# Logica_ADC.net
KiCad netlist of a schematic drawn in Altium Designer
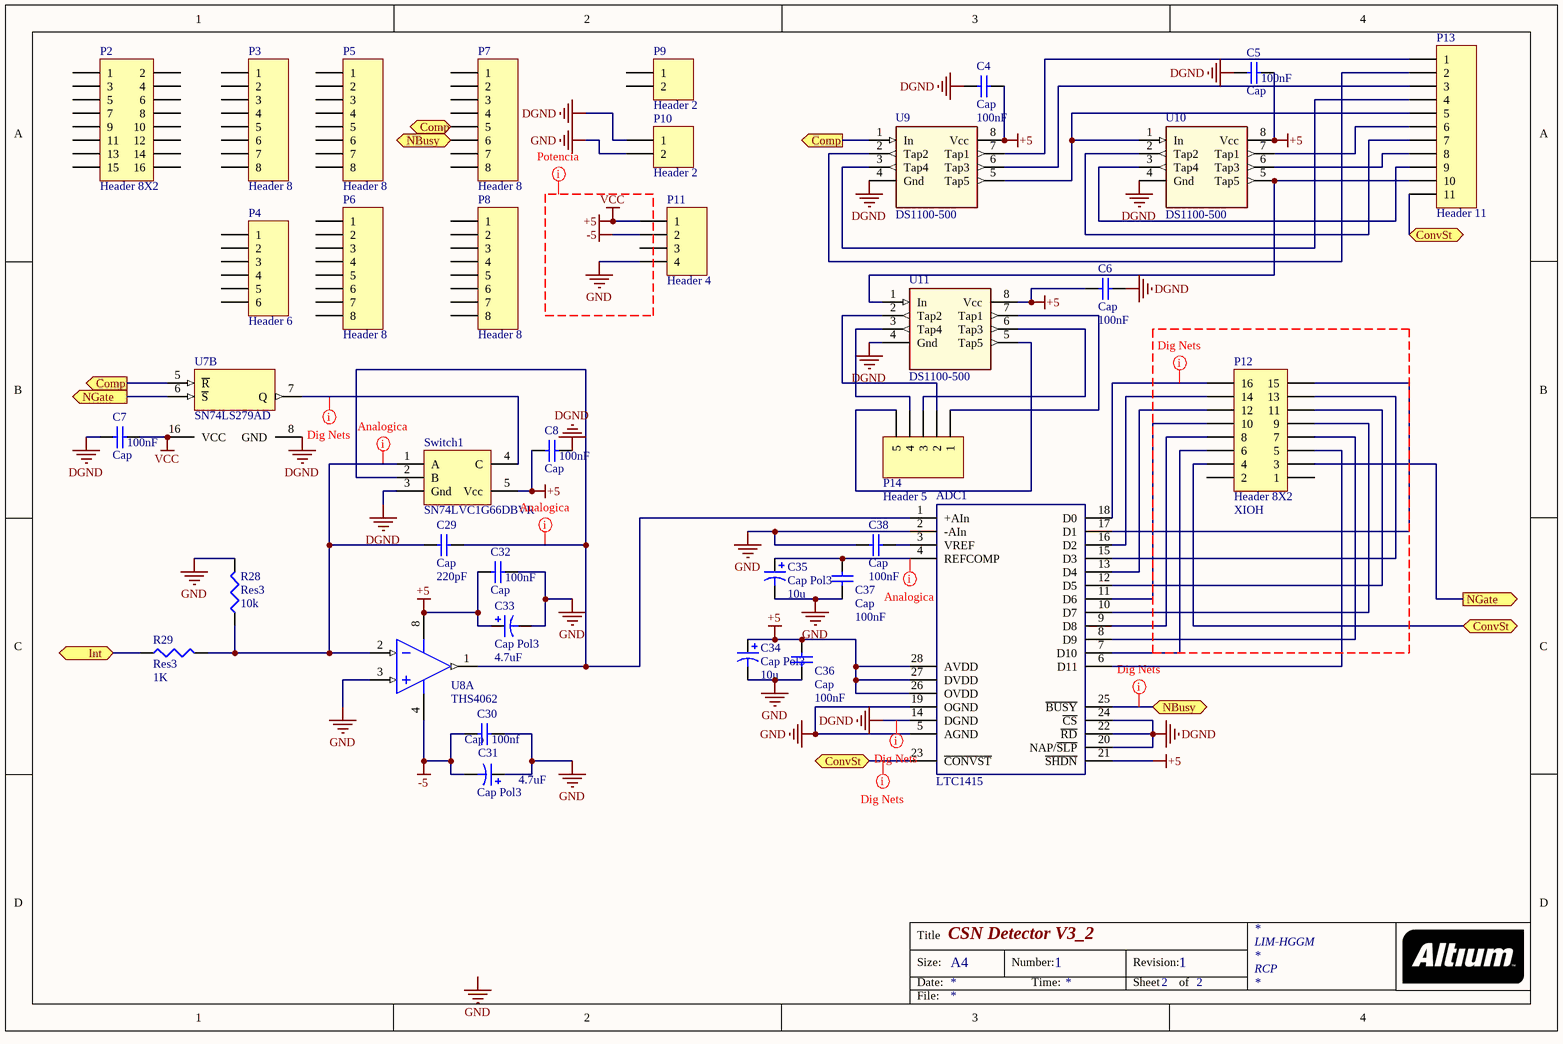
[diagram p0: Logica_ADC.SchDoc]

(export (version "E")
  (design (tool "Eeschema 10.0.6"))
  (components
    (comp (ref "ADC1")
      (value "LTC1415")
      (footprint "SO28_N")
      (libsource (lib "Integrated_Library1") (part "LTC1415"))
    )
    (comp (ref "C4")
      (value "Cap")
      (footprint "6-0805_N")
      (description "Capacitor")
      (fields (field (name "ALTIUM_VALUE") "100nF") (field (name "PUBLISHER") "Altium Limited"))
      (libsource (lib "Miscellaneous Devices") (part "Cap"))
    )
    (comp (ref "C5")
      (value "Cap")
      (footprint "6-0805_N")
      (description "Capacitor")
      (fields (field (name "ALTIUM_VALUE") "100nF") (field (name "PUBLISHER") "Altium Limited"))
      (libsource (lib "Miscellaneous Devices") (part "Cap"))
    )
    (comp (ref "C6")
      (value "Cap")
      (footprint "6-0805_N")
      (description "Capacitor")
      (fields (field (name "ALTIUM_VALUE") "100nF") (field (name "PUBLISHER") "Altium Limited"))
      (libsource (lib "Miscellaneous Devices") (part "Cap"))
    )
    (comp (ref "C7")
      (value "Cap")
      (footprint "6-0805_N")
      (description "Capacitor")
      (fields (field (name "ALTIUM_VALUE") "100nF") (field (name "PUBLISHER") "Altium Limited"))
      (libsource (lib "Miscellaneous Devices") (part "Cap"))
    )
    (comp (ref "C8")
      (value "Cap")
      (footprint "6-0805_N")
      (description "Capacitor")
      (fields (field (name "ALTIUM_VALUE") "100nF") (field (name "PUBLISHER") "Altium Limited"))
      (libsource (lib "Miscellaneous Devices") (part "Cap"))
    )
    (comp (ref "C29")
      (value "Cap")
      (footprint "6-0805_N")
      (description "Capacitor")
      (fields (field (name "ALTIUM_VALUE") "220pF") (field (name "PUBLISHER") "Altium Limited"))
      (libsource (lib "Miscellaneous Devices") (part "Cap"))
    )
    (comp (ref "C30")
      (value "Cap")
      (footprint "6-0805_N")
      (description "Capacitor")
      (fields (field (name "ALTIUM_VALUE") "100nf") (field (name "PUBLISHER") "Altium Limited"))
      (libsource (lib "Miscellaneous Devices") (part "Cap"))
    )
    (comp (ref "C31")
      (value "Cap Pol3")
      (footprint "6-0805_N")
      (description "Polarized Capacitor (Surface Mount)")
      (fields (field (name "ALTIUM_VALUE") "4.7uF") (field (name "PUBLISHER") "Altium Limited"))
      (libsource (lib "Miscellaneous Devices") (part "Cap Pol3"))
    )
    (comp (ref "C32")
      (value "Cap")
      (footprint "6-0805_N")
      (description "Capacitor")
      (fields (field (name "ALTIUM_VALUE") "100nF") (field (name "PUBLISHER") "Altium Limited"))
      (libsource (lib "Miscellaneous Devices") (part "Cap"))
    )
    (comp (ref "C33")
      (value "Cap Pol3")
      (footprint "6-0805_N")
      (description "Polarized Capacitor (Surface Mount)")
      (fields (field (name "ALTIUM_VALUE") "4.7uF") (field (name "PUBLISHER") "Altium Limited"))
      (libsource (lib "Miscellaneous Devices") (part "Cap Pol3"))
    )
    (comp (ref "C34")
      (value "Cap Pol3")
      (footprint "6-0805_N")
      (description "Polarized Capacitor (Surface Mount)")
      (fields (field (name "ALTIUM_VALUE") "10u") (field (name "PUBLISHER") "Altium Limited"))
      (libsource (lib "Miscellaneous Devices") (part "Cap Pol3"))
    )
    (comp (ref "C35")
      (value "Cap Pol3")
      (footprint "6-0805_N")
      (description "Polarized Capacitor (Surface Mount)")
      (fields (field (name "ALTIUM_VALUE") "10u") (field (name "PUBLISHER") "Altium Limited"))
      (libsource (lib "Miscellaneous Devices") (part "Cap Pol3"))
    )
    (comp (ref "C36")
      (value "Cap")
      (footprint "6-0805_N")
      (description "Capacitor")
      (fields (field (name "ALTIUM_VALUE") "100nF") (field (name "PUBLISHER") "Altium Limited"))
      (libsource (lib "Miscellaneous Devices") (part "Cap"))
    )
    (comp (ref "C37")
      (value "Cap")
      (footprint "6-0805_N")
      (description "Capacitor")
      (fields (field (name "ALTIUM_VALUE") "100nF") (field (name "PUBLISHER") "Altium Limited"))
      (libsource (lib "Miscellaneous Devices") (part "Cap"))
    )
    (comp (ref "C38")
      (value "Cap")
      (footprint "6-0805_N")
      (description "Capacitor")
      (fields (field (name "ALTIUM_VALUE") "100nF") (field (name "PUBLISHER") "Altium Limited"))
      (libsource (lib "Miscellaneous Devices") (part "Cap"))
    )
    (comp (ref "P2")
      (value "Header 8X2")
      (footprint "HDR2X8")
      (description "Header, 8-Pin, Dual row")
      (fields (field (name "PUBLISHER") "Altium Limited"))
      (libsource (lib "Miscellaneous Connectors") (part "Header 8X2"))
    )
    (comp (ref "P3")
      (value "Header 8")
      (footprint "HDR1X8")
      (description "Header, 8-Pin")
      (fields (field (name "PUBLISHER") "Altium Limited"))
      (libsource (lib "Miscellaneous Connectors") (part "Header 8"))
    )
    (comp (ref "P4")
      (value "Header 6")
      (footprint "HDR1X6")
      (description "Header, 6-Pin")
      (fields (field (name "PUBLISHER") "Altium Limited"))
      (libsource (lib "Miscellaneous Connectors") (part "Header 6"))
    )
    (comp (ref "P5")
      (value "Header 8")
      (footprint "HDR1X8")
      (description "Header, 8-Pin")
      (fields (field (name "PUBLISHER") "Altium Limited"))
      (libsource (lib "Miscellaneous Connectors") (part "Header 8"))
    )
    (comp (ref "P6")
      (value "Header 8")
      (footprint "HDR1X8")
      (description "Header, 8-Pin")
      (fields (field (name "PUBLISHER") "Altium Limited"))
      (libsource (lib "Miscellaneous Connectors") (part "Header 8"))
    )
    (comp (ref "P7")
      (value "Header 8")
      (footprint "HDR1X8")
      (description "Header, 8-Pin")
      (fields (field (name "PUBLISHER") "Altium Limited"))
      (libsource (lib "Miscellaneous Connectors") (part "Header 8"))
    )
    (comp (ref "P8")
      (value "Header 8")
      (footprint "HDR1X8")
      (description "Header, 8-Pin")
      (fields (field (name "PUBLISHER") "Altium Limited"))
      (libsource (lib "Miscellaneous Connectors") (part "Header 8"))
    )
    (comp (ref "P9")
      (value "Header 2")
      (footprint "HDR1X2")
      (description "Header, 2-Pin")
      (fields (field (name "PUBLISHER") "Altium Limited"))
      (libsource (lib "Miscellaneous Connectors") (part "Header 2"))
    )
    (comp (ref "P10")
      (value "Header 2")
      (footprint "HDR1X2")
      (description "Header, 2-Pin")
      (fields (field (name "PUBLISHER") "Altium Limited"))
      (libsource (lib "Miscellaneous Connectors") (part "Header 2"))
    )
    (comp (ref "P11")
      (value "Header 4")
      (footprint "HDR1X4")
      (description "Header, 4-Pin")
      (fields (field (name "PUBLISHER") "Altium Limited"))
      (libsource (lib "Miscellaneous Connectors") (part "Header 4"))
    )
    (comp (ref "P12")
      (value "Header 8X2")
      (footprint "HDR2X8")
      (description "Header, 8-Pin, Dual row")
      (fields (field (name "CON_ARDUINO") "XIOH") (field (name "PUBLISHER") "Altium Limited"))
      (libsource (lib "") (part "Header 8X2_1"))
    )
    (comp (ref "P13")
      (value "Header 11")
      (footprint "HDR1X11")
      (description "Header, 11-Pin")
      (fields (field (name "PUBLISHER") "Altium Limited"))
      (libsource (lib "Miscellaneous Connectors") (part "Header 11"))
    )
    (comp (ref "P14")
      (value "Header 5")
      (footprint "HDR1X5")
      (description "Header, 5-Pin")
      (fields (field (name "PUBLISHER") "Altium Limited"))
      (libsource (lib "Miscellaneous Connectors") (part "Header 5"))
    )
    (comp (ref "R28")
      (value "Res3")
      (footprint "6-0805_N")
      (description "Resistor")
      (fields (field (name "ALTIUM_VALUE") "10k") (field (name "PUBLISHER") "Altium Limited"))
      (libsource (lib "Miscellaneous Devices") (part "Res3"))
    )
    (comp (ref "R29")
      (value "Res3")
      (footprint "6-0805_N")
      (description "Resistor")
      (fields (field (name "ALTIUM_VALUE") "1K") (field (name "PUBLISHER") "Altium Limited"))
      (libsource (lib "Miscellaneous Devices") (part "Res3"))
    )
    (comp (ref "Switch1")
      (value "SN74LVC1G66DBVR")
      (footprint "SOT23-5_N")
      (libsource (lib "Integrated_Library1") (part "SN74LVC1G66DBVR"))
    )
    (comp (ref "U7")
      (value "SN74LS279AD")
      (footprint "D016_N")
      (description "Quadruple S-R Latches")
      (fields (field (name "PUBLISHER") "Altium Limited"))
      (libsource (lib "TI Logic Latch") (part "SN74LS279AD"))
    )
    (comp (ref "U8")
      (value "THS4062")
      (footprint "S8_N")
      (description "Low Cost Dual Video Amplifier")
      (fields (field (name "PUBLISHER") "Altium Limited"))
      (libsource (lib "LT Video Amplifier") (part "LT1253CS8"))
    )
    (comp (ref "U9")
      (value "DS1100-500")
      (footprint "SO-8_L")
      (libsource (lib "Int_Lib1") (part "DS1100-500"))
    )
    (comp (ref "U10")
      (value "DS1100-500")
      (footprint "SO-8_L")
      (libsource (lib "Int_Lib1") (part "DS1100-500"))
    )
    (comp (ref "U11")
      (value "DS1100-500")
      (footprint "SO-8_L")
      (libsource (lib "Int_Lib1") (part "DS1100-500"))
    )
  )
  (nets
    (net (code "1") (name "+5") (class "Default")
      (node (ref "ADC1") (pin "21") (pinfunction "~{SHDN}_21") (pintype "passive"))
      (node (ref "ADC1") (pin "26") (pinfunction "OVDD_26") (pintype "passive"))
      (node (ref "ADC1") (pin "27") (pinfunction "DVDD_27") (pintype "passive"))
      (node (ref "ADC1") (pin "28") (pinfunction "AVDD_28") (pintype "passive"))
      (node (ref "C32") (pin "2") (pinfunction "2_2") (pintype "passive"))
      (node (ref "C33") (pin "1") (pinfunction "1_1") (pintype "passive"))
      (node (ref "C34") (pin "1") (pinfunction "1_1") (pintype "passive"))
      (node (ref "C36") (pin "2") (pinfunction "2_2") (pintype "passive"))
      (node (ref "C4") (pin "2") (pinfunction "2_2") (pintype "passive"))
      (node (ref "C5") (pin "1") (pinfunction "1_1") (pintype "passive"))
      (node (ref "C6") (pin "1") (pinfunction "1_1") (pintype "passive"))
      (node (ref "C7") (pin "1") (pinfunction "1_1") (pintype "passive"))
      (node (ref "C8") (pin "2") (pinfunction "2_2") (pintype "passive"))
      (node (ref "P11") (pin "1") (pinfunction "1_1") (pintype "passive"))
      (node (ref "Switch1") (pin "5") (pinfunction "Vcc_5") (pintype "passive"))
      (node (ref "U10") (pin "8") (pinfunction "Vcc_8") (pintype "power_in"))
      (node (ref "U11") (pin "8") (pinfunction "Vcc_8") (pintype "power_in"))
      (node (ref "U7") (pin "16") (pinfunction "VCC_16") (pintype "power_in"))
      (node (ref "U8") (pin "8") (pinfunction "V+_8") (pintype "power_in"))
      (node (ref "U9") (pin "8") (pinfunction "Vcc_8") (pintype "power_in"))
    )
    (net (code "2") (name "-5") (class "Default")
      (node (ref "C30") (pin "1") (pinfunction "1_1") (pintype "passive"))
      (node (ref "C31") (pin "2") (pinfunction "2_2") (pintype "passive"))
      (node (ref "P11") (pin "2") (pinfunction "2_2") (pintype "passive"))
      (node (ref "U8") (pin "4") (pinfunction "V-_4") (pintype "power_in"))
    )
    (net (code "3") (name "/Comp") (class "Default")
      (node (ref "P7") (pin "5") (pinfunction "5_5") (pintype "passive"))
      (node (ref "U7") (pin "5") (pinfunction "~{R}_5") (pintype "input"))
      (node (ref "U9") (pin "1") (pinfunction "In_1") (pintype "input"))
    )
    (net (code "4") (name "/ConvSt") (class "Default")
      (node (ref "ADC1") (pin "23") (pinfunction "~{CONVST}_23") (pintype "passive"))
      (node (ref "P12") (pin "4") (pinfunction "4_4") (pintype "passive"))
      (node (ref "P13") (pin "11") (pinfunction "11_11") (pintype "passive"))
    )
    (net (code "5") (name "/Int") (class "Default")
      (node (ref "R29") (pin "1") (pinfunction "1_1") (pintype "passive"))
    )
    (net (code "6") (name "/NBusy") (class "Default")
      (node (ref "ADC1") (pin "25") (pinfunction "~{BUSY}_25") (pintype "passive"))
      (node (ref "P7") (pin "6") (pinfunction "6_6") (pintype "passive"))
    )
    (net (code "7") (name "/NGate") (class "Default")
      (node (ref "P12") (pin "3") (pinfunction "3_3") (pintype "passive"))
      (node (ref "U7") (pin "6") (pinfunction "~{S}_6") (pintype "input"))
    )
    (net (code "8") (name "DGND") (class "Default")
      (node (ref "ADC1") (pin "14") (pinfunction "DGND_14") (pintype "passive"))
      (node (ref "ADC1") (pin "19") (pinfunction "OGND_19") (pintype "passive"))
      (node (ref "ADC1") (pin "2") (pinfunction "-AIn_2") (pintype "passive"))
      (node (ref "ADC1") (pin "20") (pinfunction "NAP/~{SLP}_20") (pintype "passive"))
      (node (ref "ADC1") (pin "22") (pinfunction "~{RD}_22") (pintype "passive"))
      (node (ref "ADC1") (pin "24") (pinfunction "~{CS}_24") (pintype "passive"))
      (node (ref "ADC1") (pin "5") (pinfunction "AGND_5") (pintype "passive"))
      (node (ref "C30") (pin "2") (pinfunction "2_2") (pintype "passive"))
      (node (ref "C31") (pin "1") (pinfunction "1_1") (pintype "passive"))
      (node (ref "C32") (pin "1") (pinfunction "1_1") (pintype "passive"))
      (node (ref "C33") (pin "2") (pinfunction "2_2") (pintype "passive"))
      (node (ref "C34") (pin "2") (pinfunction "2_2") (pintype "passive"))
      (node (ref "C35") (pin "2") (pinfunction "2_2") (pintype "passive"))
      (node (ref "C36") (pin "1") (pinfunction "1_1") (pintype "passive"))
      (node (ref "C37") (pin "1") (pinfunction "1_1") (pintype "passive"))
      (node (ref "C38") (pin "2") (pinfunction "2_2") (pintype "passive"))
      (node (ref "C4") (pin "1") (pinfunction "1_1") (pintype "passive"))
      (node (ref "C5") (pin "2") (pinfunction "2_2") (pintype "passive"))
      (node (ref "C6") (pin "2") (pinfunction "2_2") (pintype "passive"))
      (node (ref "C7") (pin "2") (pinfunction "2_2") (pintype "passive"))
      (node (ref "C8") (pin "1") (pinfunction "1_1") (pintype "passive"))
      (node (ref "P10") (pin "1") (pinfunction "1_1") (pintype "passive"))
      (node (ref "P10") (pin "2") (pinfunction "2_2") (pintype "passive"))
      (node (ref "P11") (pin "4") (pinfunction "4_4") (pintype "passive"))
      (node (ref "R28") (pin "2") (pinfunction "2_2") (pintype "passive"))
      (node (ref "Switch1") (pin "3") (pinfunction "Gnd_3") (pintype "passive"))
      (node (ref "U10") (pin "4") (pinfunction "Gnd_4") (pintype "power_in"))
      (node (ref "U11") (pin "4") (pinfunction "Gnd_4") (pintype "power_in"))
      (node (ref "U7") (pin "8") (pinfunction "GND_8") (pintype "power_in"))
      (node (ref "U8") (pin "3") (pinfunction "IN+_3") (pintype "input"))
      (node (ref "U9") (pin "4") (pinfunction "Gnd_4") (pintype "power_in"))
    )
    (net (code "9") (name "Net-(ADC1-+AIn)") (class "Default")
      (node (ref "ADC1") (pin "1") (pinfunction "+AIn_1") (pintype "passive"))
      (node (ref "C29") (pin "2") (pinfunction "2_2") (pintype "passive"))
      (node (ref "Switch1") (pin "2") (pinfunction "B_2") (pintype "passive"))
      (node (ref "U8") (pin "1") (pinfunction "OUT_1") (pintype "output"))
    )
    (net (code "10") (name "Net-(ADC1-D0)") (class "Default")
      (node (ref "ADC1") (pin "18") (pinfunction "D0_18") (pintype "passive"))
      (node (ref "P12") (pin "16") (pinfunction "16_16") (pintype "passive"))
    )
    (net (code "11") (name "Net-(ADC1-D1)") (class "Default")
      (node (ref "ADC1") (pin "17") (pinfunction "D1_17") (pintype "passive"))
      (node (ref "P12") (pin "15") (pinfunction "15_15") (pintype "passive"))
    )
    (net (code "12") (name "Net-(ADC1-D2)") (class "Default")
      (node (ref "ADC1") (pin "16") (pinfunction "D2_16") (pintype "passive"))
      (node (ref "P12") (pin "14") (pinfunction "14_14") (pintype "passive"))
    )
    (net (code "13") (name "Net-(ADC1-D3)") (class "Default")
      (node (ref "ADC1") (pin "15") (pinfunction "D3_15") (pintype "passive"))
      (node (ref "P12") (pin "13") (pinfunction "13_13") (pintype "passive"))
    )
    (net (code "14") (name "Net-(ADC1-D4)") (class "Default")
      (node (ref "ADC1") (pin "13") (pinfunction "D4_13") (pintype "passive"))
      (node (ref "P12") (pin "12") (pinfunction "12_12") (pintype "passive"))
    )
    (net (code "15") (name "Net-(ADC1-D5)") (class "Default")
      (node (ref "ADC1") (pin "12") (pinfunction "D5_12") (pintype "passive"))
      (node (ref "P12") (pin "11") (pinfunction "11_11") (pintype "passive"))
    )
    (net (code "16") (name "Net-(ADC1-D6)") (class "Default")
      (node (ref "ADC1") (pin "11") (pinfunction "D6_11") (pintype "passive"))
      (node (ref "P12") (pin "10") (pinfunction "10_10") (pintype "passive"))
    )
    (net (code "17") (name "Net-(ADC1-D7)") (class "Default")
      (node (ref "ADC1") (pin "10") (pinfunction "D7_10") (pintype "passive"))
      (node (ref "P12") (pin "9") (pinfunction "9_9") (pintype "passive"))
    )
    (net (code "18") (name "Net-(ADC1-D8)") (class "Default")
      (node (ref "ADC1") (pin "9") (pinfunction "D8_9") (pintype "passive"))
      (node (ref "P12") (pin "8") (pinfunction "8_8") (pintype "passive"))
    )
    (net (code "19") (name "Net-(ADC1-D9)") (class "Default")
      (node (ref "ADC1") (pin "8") (pinfunction "D9_8") (pintype "passive"))
      (node (ref "P12") (pin "7") (pinfunction "7_7") (pintype "passive"))
    )
    (net (code "20") (name "Net-(ADC1-D10)") (class "Default")
      (node (ref "ADC1") (pin "7") (pinfunction "D10_7") (pintype "passive"))
      (node (ref "P12") (pin "6") (pinfunction "6_6") (pintype "passive"))
    )
    (net (code "21") (name "Net-(ADC1-D11)") (class "Default")
      (node (ref "ADC1") (pin "6") (pinfunction "D11_6") (pintype "passive"))
      (node (ref "P12") (pin "5") (pinfunction "5_5") (pintype "passive"))
    )
    (net (code "22") (name "Net-(ADC1-REFCOMP)") (class "Default")
      (node (ref "ADC1") (pin "4") (pinfunction "REFCOMP_4") (pintype "passive"))
      (node (ref "C35") (pin "1") (pinfunction "1_1") (pintype "passive"))
      (node (ref "C37") (pin "2") (pinfunction "2_2") (pintype "passive"))
    )
    (net (code "23") (name "Net-(ADC1-VREF)") (class "Default")
      (node (ref "ADC1") (pin "3") (pinfunction "VREF_3") (pintype "passive"))
      (node (ref "C38") (pin "1") (pinfunction "1_1") (pintype "passive"))
    )
    (net (code "24") (name "Net-(Switch1-A)") (class "Default")
      (node (ref "C29") (pin "1") (pinfunction "1_1") (pintype "passive"))
      (node (ref "R28") (pin "1") (pinfunction "1_1") (pintype "passive"))
      (node (ref "R29") (pin "2") (pinfunction "2_2") (pintype "passive"))
      (node (ref "Switch1") (pin "1") (pinfunction "A_1") (pintype "passive"))
      (node (ref "U8") (pin "2") (pinfunction "IN-_2") (pintype "input"))
    )
    (net (code "25") (name "Net-(Switch1-C)") (class "Default")
      (node (ref "Switch1") (pin "4") (pinfunction "C_4") (pintype "passive"))
      (node (ref "U7") (pin "7") (pinfunction "Q_7") (pintype "output"))
    )
    (net (code "26") (name "Net-(U9-Tap1)") (class "Default")
      (node (ref "P13") (pin "1") (pinfunction "1_1") (pintype "passive"))
      (node (ref "U9") (pin "7") (pinfunction "Tap1_7") (pintype "output"))
    )
    (net (code "27") (name "Net-(U9-Tap2)") (class "Default")
      (node (ref "P13") (pin "2") (pinfunction "2_2") (pintype "passive"))
      (node (ref "U9") (pin "2") (pinfunction "Tap2_2") (pintype "output"))
    )
    (net (code "28") (name "Net-(U9-Tap3)") (class "Default")
      (node (ref "P13") (pin "3") (pinfunction "3_3") (pintype "passive"))
      (node (ref "U9") (pin "6") (pinfunction "Tap3_6") (pintype "output"))
    )
    (net (code "29") (name "Net-(U9-Tap4)") (class "Default")
      (node (ref "P13") (pin "4") (pinfunction "4_4") (pintype "passive"))
      (node (ref "U9") (pin "3") (pinfunction "Tap4_3") (pintype "output"))
    )
    (net (code "30") (name "Net-(U10-In)") (class "Default")
      (node (ref "P13") (pin "5") (pinfunction "5_5") (pintype "passive"))
      (node (ref "U10") (pin "1") (pinfunction "In_1") (pintype "input"))
      (node (ref "U9") (pin "5") (pinfunction "Tap5_5") (pintype "output"))
    )
    (net (code "31") (name "Net-(U10-Tap1)") (class "Default")
      (node (ref "P13") (pin "6") (pinfunction "6_6") (pintype "passive"))
      (node (ref "U10") (pin "7") (pinfunction "Tap1_7") (pintype "output"))
    )
    (net (code "32") (name "Net-(U10-Tap2)") (class "Default")
      (node (ref "P13") (pin "7") (pinfunction "7_7") (pintype "passive"))
      (node (ref "U10") (pin "2") (pinfunction "Tap2_2") (pintype "output"))
    )
    (net (code "33") (name "Net-(U10-Tap3)") (class "Default")
      (node (ref "P13") (pin "8") (pinfunction "8_8") (pintype "passive"))
      (node (ref "U10") (pin "6") (pinfunction "Tap3_6") (pintype "output"))
    )
    (net (code "34") (name "Net-(U10-Tap4)") (class "Default")
      (node (ref "P13") (pin "9") (pinfunction "9_9") (pintype "passive"))
      (node (ref "U10") (pin "3") (pinfunction "Tap4_3") (pintype "output"))
    )
    (net (code "35") (name "Net-(U10-Tap5)") (class "Default")
      (node (ref "P13") (pin "10") (pinfunction "10_10") (pintype "passive"))
      (node (ref "U10") (pin "5") (pinfunction "Tap5_5") (pintype "output"))
      (node (ref "U11") (pin "1") (pinfunction "In_1") (pintype "input"))
    )
    (net (code "36") (name "Net-(U11-Tap1)") (class "Default")
      (node (ref "P14") (pin "1") (pinfunction "1_1") (pintype "passive"))
      (node (ref "U11") (pin "7") (pinfunction "Tap1_7") (pintype "output"))
    )
    (net (code "37") (name "Net-(U11-Tap2)") (class "Default")
      (node (ref "P14") (pin "2") (pinfunction "2_2") (pintype "passive"))
      (node (ref "U11") (pin "2") (pinfunction "Tap2_2") (pintype "output"))
    )
    (net (code "38") (name "Net-(U11-Tap3)") (class "Default")
      (node (ref "P14") (pin "3") (pinfunction "3_3") (pintype "passive"))
      (node (ref "U11") (pin "6") (pinfunction "Tap3_6") (pintype "output"))
    )
    (net (code "39") (name "Net-(U11-Tap4)") (class "Default")
      (node (ref "P14") (pin "4") (pinfunction "4_4") (pintype "passive"))
      (node (ref "U11") (pin "3") (pinfunction "Tap4_3") (pintype "output"))
    )
    (net (code "40") (name "Net-(U11-Tap5)") (class "Default")
      (node (ref "P14") (pin "5") (pinfunction "5_5") (pintype "passive"))
      (node (ref "U11") (pin "5") (pinfunction "Tap5_5") (pintype "output"))
    )
    (net (code "41") (name "unconnected-(P2-Pad1)") (class "Default")
      (node (ref "P2") (pin "1") (pinfunction "1_1") (pintype "passive"))
    )
    (net (code "42") (name "unconnected-(P2-Pad2)") (class "Default")
      (node (ref "P2") (pin "2") (pinfunction "2_2") (pintype "passive"))
    )
    (net (code "43") (name "unconnected-(P2-Pad3)") (class "Default")
      (node (ref "P2") (pin "3") (pinfunction "3_3") (pintype "passive"))
    )
    (net (code "44") (name "unconnected-(P2-Pad4)") (class "Default")
      (node (ref "P2") (pin "4") (pinfunction "4_4") (pintype "passive"))
    )
    (net (code "45") (name "unconnected-(P2-Pad5)") (class "Default")
      (node (ref "P2") (pin "5") (pinfunction "5_5") (pintype "passive"))
    )
    (net (code "46") (name "unconnected-(P2-Pad6)") (class "Default")
      (node (ref "P2") (pin "6") (pinfunction "6_6") (pintype "passive"))
    )
    (net (code "47") (name "unconnected-(P2-Pad7)") (class "Default")
      (node (ref "P2") (pin "7") (pinfunction "7_7") (pintype "passive"))
    )
    (net (code "48") (name "unconnected-(P2-Pad8)") (class "Default")
      (node (ref "P2") (pin "8") (pinfunction "8_8") (pintype "passive"))
    )
    (net (code "49") (name "unconnected-(P2-Pad9)") (class "Default")
      (node (ref "P2") (pin "9") (pinfunction "9_9") (pintype "passive"))
    )
    (net (code "50") (name "unconnected-(P2-Pad10)") (class "Default")
      (node (ref "P2") (pin "10") (pinfunction "10_10") (pintype "passive"))
    )
    (net (code "51") (name "unconnected-(P2-Pad11)") (class "Default")
      (node (ref "P2") (pin "11") (pinfunction "11_11") (pintype "passive"))
    )
    (net (code "52") (name "unconnected-(P2-Pad12)") (class "Default")
      (node (ref "P2") (pin "12") (pinfunction "12_12") (pintype "passive"))
    )
    (net (code "53") (name "unconnected-(P2-Pad13)") (class "Default")
      (node (ref "P2") (pin "13") (pinfunction "13_13") (pintype "passive"))
    )
    (net (code "54") (name "unconnected-(P2-Pad14)") (class "Default")
      (node (ref "P2") (pin "14") (pinfunction "14_14") (pintype "passive"))
    )
    (net (code "55") (name "unconnected-(P2-Pad15)") (class "Default")
      (node (ref "P2") (pin "15") (pinfunction "15_15") (pintype "passive"))
    )
    (net (code "56") (name "unconnected-(P2-Pad16)") (class "Default")
      (node (ref "P2") (pin "16") (pinfunction "16_16") (pintype "passive"))
    )
    (net (code "57") (name "unconnected-(P3-Pad1)") (class "Default")
      (node (ref "P3") (pin "1") (pinfunction "1_1") (pintype "passive"))
    )
    (net (code "58") (name "unconnected-(P3-Pad2)") (class "Default")
      (node (ref "P3") (pin "2") (pinfunction "2_2") (pintype "passive"))
    )
    (net (code "59") (name "unconnected-(P3-Pad3)") (class "Default")
      (node (ref "P3") (pin "3") (pinfunction "3_3") (pintype "passive"))
    )
    (net (code "60") (name "unconnected-(P3-Pad4)") (class "Default")
      (node (ref "P3") (pin "4") (pinfunction "4_4") (pintype "passive"))
    )
    (net (code "61") (name "unconnected-(P3-Pad5)") (class "Default")
      (node (ref "P3") (pin "5") (pinfunction "5_5") (pintype "passive"))
    )
    (net (code "62") (name "unconnected-(P3-Pad6)") (class "Default")
      (node (ref "P3") (pin "6") (pinfunction "6_6") (pintype "passive"))
    )
    (net (code "63") (name "unconnected-(P3-Pad7)") (class "Default")
      (node (ref "P3") (pin "7") (pinfunction "7_7") (pintype "passive"))
    )
    (net (code "64") (name "unconnected-(P3-Pad8)") (class "Default")
      (node (ref "P3") (pin "8") (pinfunction "8_8") (pintype "passive"))
    )
    (net (code "65") (name "unconnected-(P4-Pad1)") (class "Default")
      (node (ref "P4") (pin "1") (pinfunction "1_1") (pintype "passive"))
    )
    (net (code "66") (name "unconnected-(P4-Pad2)") (class "Default")
      (node (ref "P4") (pin "2") (pinfunction "2_2") (pintype "passive"))
    )
    (net (code "67") (name "unconnected-(P4-Pad3)") (class "Default")
      (node (ref "P4") (pin "3") (pinfunction "3_3") (pintype "passive"))
    )
    (net (code "68") (name "unconnected-(P4-Pad4)") (class "Default")
      (node (ref "P4") (pin "4") (pinfunction "4_4") (pintype "passive"))
    )
    (net (code "69") (name "unconnected-(P4-Pad5)") (class "Default")
      (node (ref "P4") (pin "5") (pinfunction "5_5") (pintype "passive"))
    )
    (net (code "70") (name "unconnected-(P4-Pad6)") (class "Default")
      (node (ref "P4") (pin "6") (pinfunction "6_6") (pintype "passive"))
    )
    (net (code "71") (name "unconnected-(P5-Pad1)") (class "Default")
      (node (ref "P5") (pin "1") (pinfunction "1_1") (pintype "passive"))
    )
    (net (code "72") (name "unconnected-(P5-Pad2)") (class "Default")
      (node (ref "P5") (pin "2") (pinfunction "2_2") (pintype "passive"))
    )
    (net (code "73") (name "unconnected-(P5-Pad3)") (class "Default")
      (node (ref "P5") (pin "3") (pinfunction "3_3") (pintype "passive"))
    )
    (net (code "74") (name "unconnected-(P5-Pad4)") (class "Default")
      (node (ref "P5") (pin "4") (pinfunction "4_4") (pintype "passive"))
    )
    (net (code "75") (name "unconnected-(P5-Pad5)") (class "Default")
      (node (ref "P5") (pin "5") (pinfunction "5_5") (pintype "passive"))
    )
    (net (code "76") (name "unconnected-(P5-Pad6)") (class "Default")
      (node (ref "P5") (pin "6") (pinfunction "6_6") (pintype "passive"))
    )
    (net (code "77") (name "unconnected-(P5-Pad7)") (class "Default")
      (node (ref "P5") (pin "7") (pinfunction "7_7") (pintype "passive"))
    )
    (net (code "78") (name "unconnected-(P5-Pad8)") (class "Default")
      (node (ref "P5") (pin "8") (pinfunction "8_8") (pintype "passive"))
    )
    (net (code "79") (name "unconnected-(P6-Pad1)") (class "Default")
      (node (ref "P6") (pin "1") (pinfunction "1_1") (pintype "passive"))
    )
    (net (code "80") (name "unconnected-(P6-Pad2)") (class "Default")
      (node (ref "P6") (pin "2") (pinfunction "2_2") (pintype "passive"))
    )
    (net (code "81") (name "unconnected-(P6-Pad3)") (class "Default")
      (node (ref "P6") (pin "3") (pinfunction "3_3") (pintype "passive"))
    )
    (net (code "82") (name "unconnected-(P6-Pad4)") (class "Default")
      (node (ref "P6") (pin "4") (pinfunction "4_4") (pintype "passive"))
    )
    (net (code "83") (name "unconnected-(P6-Pad5)") (class "Default")
      (node (ref "P6") (pin "5") (pinfunction "5_5") (pintype "passive"))
    )
    (net (code "84") (name "unconnected-(P6-Pad6)") (class "Default")
      (node (ref "P6") (pin "6") (pinfunction "6_6") (pintype "passive"))
    )
    (net (code "85") (name "unconnected-(P6-Pad7)") (class "Default")
      (node (ref "P6") (pin "7") (pinfunction "7_7") (pintype "passive"))
    )
    (net (code "86") (name "unconnected-(P6-Pad8)") (class "Default")
      (node (ref "P6") (pin "8") (pinfunction "8_8") (pintype "passive"))
    )
    (net (code "87") (name "unconnected-(P7-Pad1)") (class "Default")
      (node (ref "P7") (pin "1") (pinfunction "1_1") (pintype "passive"))
    )
    (net (code "88") (name "unconnected-(P7-Pad2)") (class "Default")
      (node (ref "P7") (pin "2") (pinfunction "2_2") (pintype "passive"))
    )
    (net (code "89") (name "unconnected-(P7-Pad3)") (class "Default")
      (node (ref "P7") (pin "3") (pinfunction "3_3") (pintype "passive"))
    )
    (net (code "90") (name "unconnected-(P7-Pad4)") (class "Default")
      (node (ref "P7") (pin "4") (pinfunction "4_4") (pintype "passive"))
    )
    (net (code "91") (name "unconnected-(P7-Pad7)") (class "Default")
      (node (ref "P7") (pin "7") (pinfunction "7_7") (pintype "passive"))
    )
    (net (code "92") (name "unconnected-(P7-Pad8)") (class "Default")
      (node (ref "P7") (pin "8") (pinfunction "8_8") (pintype "passive"))
    )
    (net (code "93") (name "unconnected-(P8-Pad1)") (class "Default")
      (node (ref "P8") (pin "1") (pinfunction "1_1") (pintype "passive"))
    )
    (net (code "94") (name "unconnected-(P8-Pad2)") (class "Default")
      (node (ref "P8") (pin "2") (pinfunction "2_2") (pintype "passive"))
    )
    (net (code "95") (name "unconnected-(P8-Pad3)") (class "Default")
      (node (ref "P8") (pin "3") (pinfunction "3_3") (pintype "passive"))
    )
    (net (code "96") (name "unconnected-(P8-Pad4)") (class "Default")
      (node (ref "P8") (pin "4") (pinfunction "4_4") (pintype "passive"))
    )
    (net (code "97") (name "unconnected-(P8-Pad5)") (class "Default")
      (node (ref "P8") (pin "5") (pinfunction "5_5") (pintype "passive"))
    )
    (net (code "98") (name "unconnected-(P8-Pad6)") (class "Default")
      (node (ref "P8") (pin "6") (pinfunction "6_6") (pintype "passive"))
    )
    (net (code "99") (name "unconnected-(P8-Pad7)") (class "Default")
      (node (ref "P8") (pin "7") (pinfunction "7_7") (pintype "passive"))
    )
    (net (code "100") (name "unconnected-(P8-Pad8)") (class "Default")
      (node (ref "P8") (pin "8") (pinfunction "8_8") (pintype "passive"))
    )
    (net (code "101") (name "unconnected-(P9-Pad1)") (class "Default")
      (node (ref "P9") (pin "1") (pinfunction "1_1") (pintype "passive"))
    )
    (net (code "102") (name "unconnected-(P9-Pad2)") (class "Default")
      (node (ref "P9") (pin "2") (pinfunction "2_2") (pintype "passive"))
    )
    (net (code "103") (name "unconnected-(P11-Pad3)") (class "Default")
      (node (ref "P11") (pin "3") (pinfunction "3_3") (pintype "passive"))
    )
    (net (code "104") (name "unconnected-(P12-Pad1)") (class "Default")
      (node (ref "P12") (pin "1") (pinfunction "1_1") (pintype "passive"))
    )
    (net (code "105") (name "unconnected-(P12-Pad2)") (class "Default")
      (node (ref "P12") (pin "2") (pinfunction "2_2") (pintype "passive"))
    )
  )
)
